# Door-inner.net
KiCad netlist of a schematic drawn in EAGLE
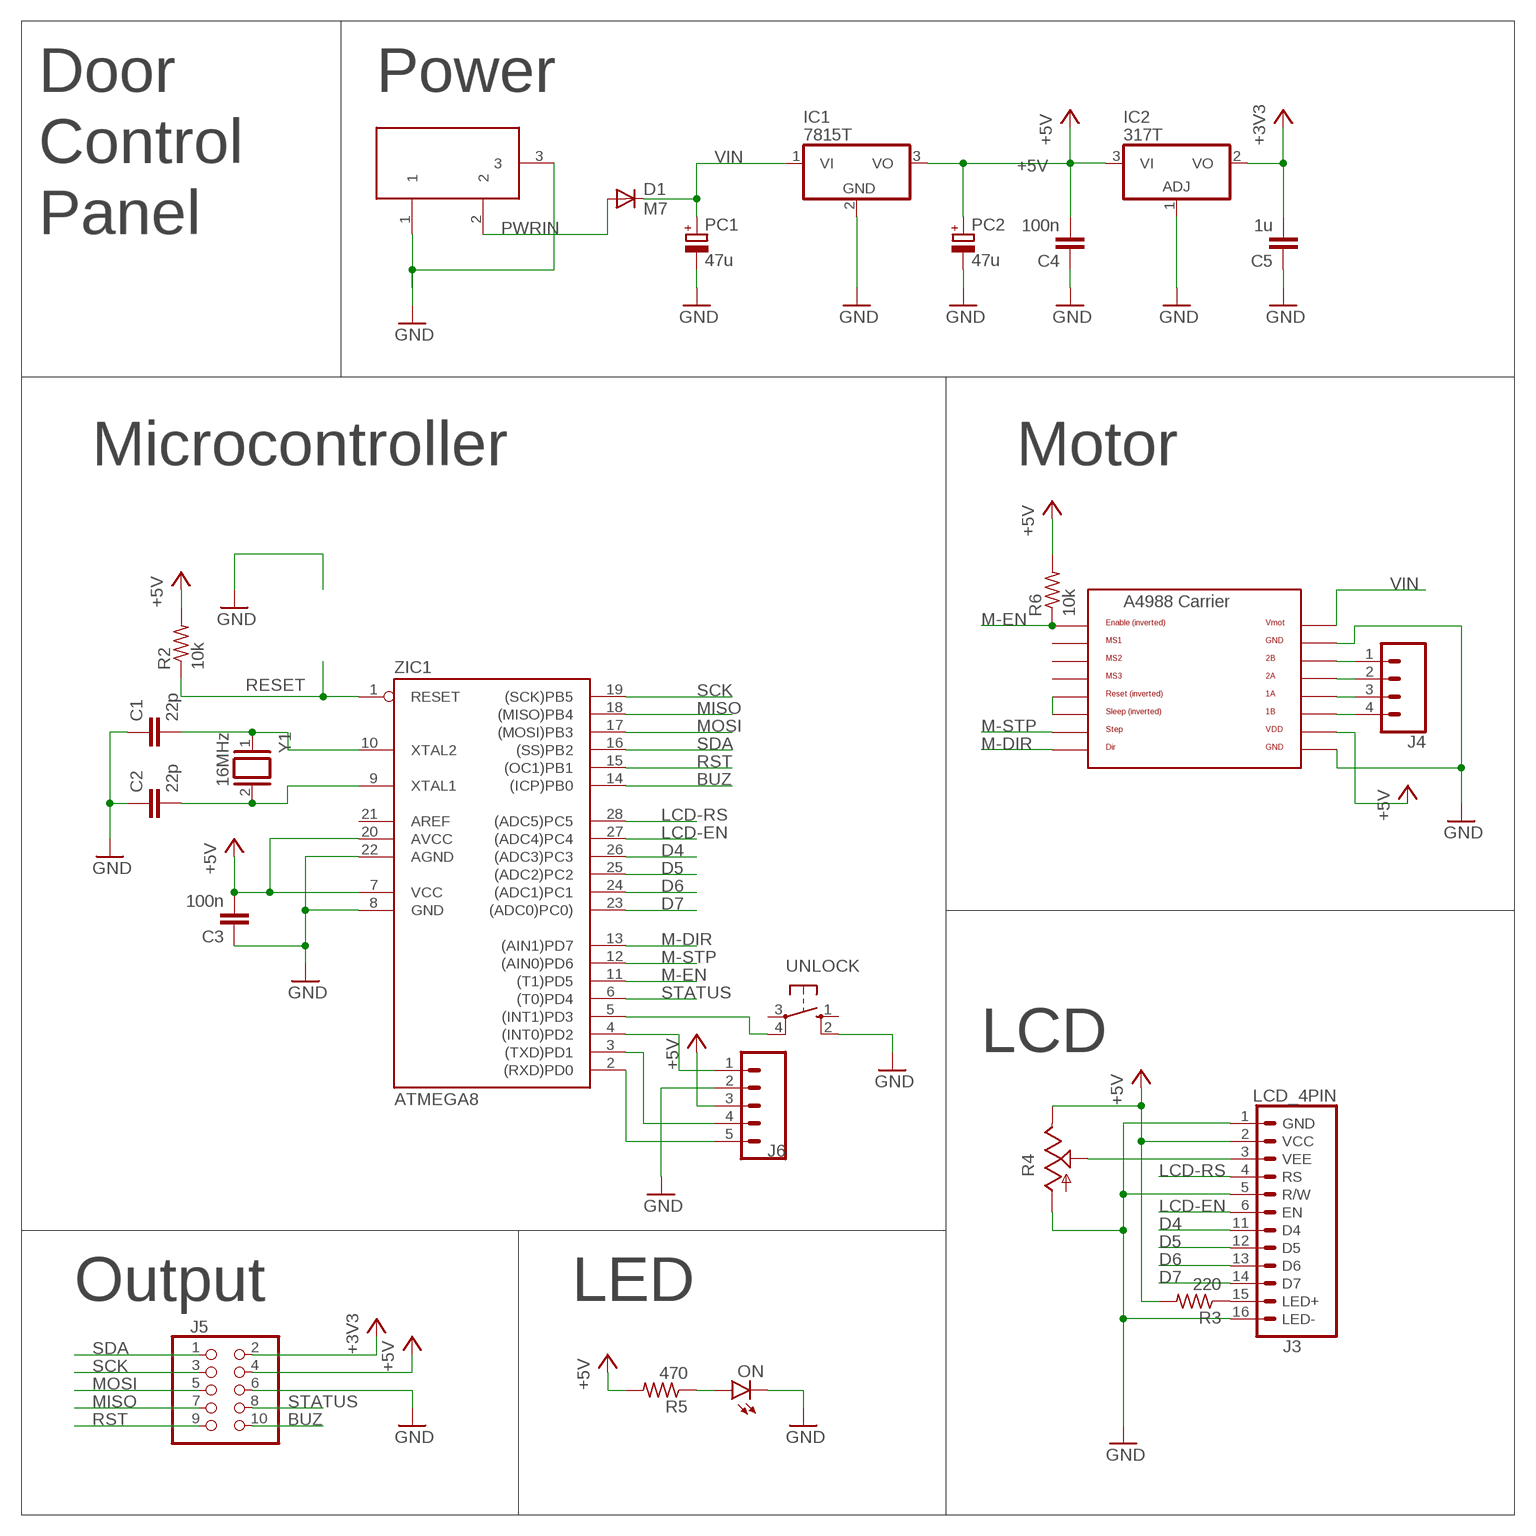
[diagram p0: schematic, sheet 1]

(export (version "E")
  (design (tool "Eeschema 10.0.6"))
  (components
    (comp (ref "C1")
      (value "22p")
      (footprint "eagle-import:C025-030X050")
      (libsource (lib "eagle-import") (part "C-EU025-030X050"))
    )
    (comp (ref "C2")
      (value "22p")
      (footprint "eagle-import:C025-030X050")
      (libsource (lib "eagle-import") (part "C-EU025-030X050"))
    )
    (comp (ref "C3")
      (value "100n")
      (footprint "eagle-import:C050-030X075")
      (libsource (lib "eagle-import") (part "C-EU050-030X075"))
    )
    (comp (ref "C4")
      (value "100n")
      (footprint "eagle-import:C050-030X075")
      (libsource (lib "eagle-import") (part "C-EU050-030X075"))
    )
    (comp (ref "C5")
      (value "1u")
      (footprint "eagle-import:C050-030X075")
      (libsource (lib "eagle-import") (part "C-EU050-030X075"))
    )
    (comp (ref "D1")
      (value "M7")
      (footprint "eagle-import:D-12.5")
      (libsource (lib "eagle-import") (part "DIODE-D-12.5"))
    )
    (comp (ref "IC1")
      (value "7815T")
      (footprint "eagle-import:TO220H")
      (libsource (lib "eagle-import") (part "78T15"))
    )
    (comp (ref "IC2")
      (value "317T")
      (footprint "eagle-import:TO220H")
      (libsource (lib "eagle-import") (part "317T"))
    )
    (comp (ref "J3")
      (value "LCD_4PIN")
      (footprint "eagle-import:LCD-16X2")
      (libsource (lib "eagle-import") (part "LCD_4PIN"))
    )
    (comp (ref "J4")
      (value "CONN_04")
      (footprint "eagle-import:1X04")
      (libsource (lib "eagle-import") (part "CONN_04"))
    )
    (comp (ref "J5")
      (value "PINHD-2X5")
      (footprint "eagle-import:2X05")
      (libsource (lib "eagle-import") (part "PINHD-2X5"))
    )
    (comp (ref "J6")
      (value "CONN_05")
      (footprint "eagle-import:1X05")
      (libsource (lib "eagle-import") (part "CONN_05"))
    )
    (comp (ref "ON")
      (value "LED3MM")
      (footprint "eagle-import:LED3MM")
      (libsource (lib "eagle-import") (part "LED3MM"))
    )
    (comp (ref "PC1")
      (value "47u")
      (footprint "eagle-import:TT2D5")
      (libsource (lib "eagle-import") (part "CPOL-EUTT2D5"))
    )
    (comp (ref "PC2")
      (value "47u")
      (footprint "eagle-import:TT2D5")
      (libsource (lib "eagle-import") (part "CPOL-EUTT2D5"))
    )
    (comp (ref "R2")
      (value "10k")
      (footprint "eagle-import:0207_10")
      (libsource (lib "eagle-import") (part "R-US_0207/10"))
    )
    (comp (ref "R3")
      (value "220")
      (footprint "eagle-import:0207_10")
      (libsource (lib "eagle-import") (part "R-US_0207/10"))
    )
    (comp (ref "R4")
      (value "TRIM_US-S63P")
      (footprint "eagle-import:S63P")
      (libsource (lib "eagle-import") (part "TRIM_US-S63P"))
    )
    (comp (ref "R5")
      (value "470")
      (footprint "eagle-import:0207_10")
      (libsource (lib "eagle-import") (part "R-US_0207/10"))
    )
    (comp (ref "R6")
      (value "10k")
      (footprint "eagle-import:0207_10")
      (libsource (lib "eagle-import") (part "R-US_0207/10"))
    )
    (comp (ref "U$1")
      (value "A4988BREAKOUT")
      (footprint "eagle-import:A4988BREAKOUT")
      (libsource (lib "eagle-import") (part "A4988BREAKOUT"))
    )
    (comp (ref "UNLOCK")
      (value "10-XX")
      (footprint "eagle-import:B3F-10XX")
      (fields (field (name "MPN") "B3F-1000"))
      (libsource (lib "eagle-import") (part "10-XX"))
    )
    (comp (ref "X1")
      (value "POWERSUPPLY_DC21MMX")
      (footprint "eagle-import:POWERSUPPLY_DC-21MM")
      (libsource (lib "eagle-import") (part "POWERSUPPLY_DC21MMX"))
    )
    (comp (ref "Y1")
      (value "16MHz")
      (footprint "eagle-import:QS")
      (libsource (lib "eagle-import") (part "XTAL/S"))
    )
    (comp (ref "ZIC1")
      (value "ATMEGA8")
      (footprint "eagle-import:DIL28-3")
      (libsource (lib "eagle-import") (part "AT90S4433P"))
    )
  )
  (nets
    (net (code "1") (name "+3V3") (class "Default")
      (node (ref "C5") (pin "2") (pinfunction "2_2") (pintype "passive"))
      (node (ref "IC2") (pin "2") (pinfunction "VO_2") (pintype "passive"))
      (node (ref "J5") (pin "2") (pinfunction "2_2") (pintype "passive"))
    )
    (net (code "2") (name "+5V") (class "Default")
      (node (ref "C3") (pin "2") (pinfunction "2_2") (pintype "passive"))
      (node (ref "C4") (pin "2") (pinfunction "2_2") (pintype "passive"))
      (node (ref "IC1") (pin "3") (pinfunction "VO_3") (pintype "passive"))
      (node (ref "IC2") (pin "3") (pinfunction "VI_3") (pintype "input"))
      (node (ref "J3") (pin "2") (pinfunction "VCC_2") (pintype "passive"))
      (node (ref "J5") (pin "4") (pinfunction "4_4") (pintype "passive"))
      (node (ref "J6") (pin "3") (pinfunction "3_3") (pintype "passive"))
      (node (ref "PC2") (pin "+") (pinfunction "+_+") (pintype "passive"))
      (node (ref "R2") (pin "2") (pinfunction "2_2") (pintype "passive"))
      (node (ref "R3") (pin "2") (pinfunction "2_2") (pintype "passive"))
      (node (ref "R4") (pin "E") (pinfunction "E_E") (pintype "passive"))
      (node (ref "R5") (pin "2") (pinfunction "2_2") (pintype "passive"))
      (node (ref "R6") (pin "2") (pinfunction "2_2") (pintype "passive"))
      (node (ref "U$1") (pin "VDD") (pinfunction "VDD_VDD") (pintype "power_in"))
      (node (ref "ZIC1") (pin "20") (pinfunction "AVCC_20") (pintype "power_in"))
      (node (ref "ZIC1") (pin "7") (pinfunction "VCC_7") (pintype "power_in"))
    )
    (net (code "3") (name "/BUZ") (class "Default")
      (node (ref "J5") (pin "10") (pinfunction "10_10") (pintype "passive"))
      (node (ref "ZIC1") (pin "14") (pinfunction "(ICP)PB0_14") (pintype "bidirectional"))
    )
    (net (code "4") (name "/D4") (class "Default")
      (node (ref "J3") (pin "11") (pinfunction "D4_11") (pintype "passive"))
      (node (ref "ZIC1") (pin "26") (pinfunction "(ADC3)PC3_26") (pintype "bidirectional"))
    )
    (net (code "5") (name "/D5") (class "Default")
      (node (ref "J3") (pin "12") (pinfunction "D5_12") (pintype "passive"))
      (node (ref "ZIC1") (pin "25") (pinfunction "(ADC2)PC2_25") (pintype "bidirectional"))
    )
    (net (code "6") (name "/D6") (class "Default")
      (node (ref "J3") (pin "13") (pinfunction "D6_13") (pintype "passive"))
      (node (ref "ZIC1") (pin "24") (pinfunction "(ADC1)PC1_24") (pintype "bidirectional"))
    )
    (net (code "7") (name "/D7") (class "Default")
      (node (ref "J3") (pin "14") (pinfunction "D7_14") (pintype "passive"))
      (node (ref "ZIC1") (pin "23") (pinfunction "(ADC0)PC0)_23") (pintype "bidirectional"))
    )
    (net (code "8") (name "/LCD-EN") (class "Default")
      (node (ref "J3") (pin "6") (pinfunction "EN_6") (pintype "passive"))
      (node (ref "ZIC1") (pin "27") (pinfunction "(ADC4)PC4_27") (pintype "bidirectional"))
    )
    (net (code "9") (name "/LCD-RS") (class "Default")
      (node (ref "J3") (pin "4") (pinfunction "RS_4") (pintype "passive"))
      (node (ref "ZIC1") (pin "28") (pinfunction "(ADC5)PC5_28") (pintype "bidirectional"))
    )
    (net (code "10") (name "/M-DIR") (class "Default")
      (node (ref "U$1") (pin "DIR") (pinfunction "DIR_DIR") (pintype "input"))
      (node (ref "ZIC1") (pin "13") (pinfunction "(AIN1)PD7_13") (pintype "bidirectional"))
    )
    (net (code "11") (name "/M-EN") (class "Default")
      (node (ref "R6") (pin "1") (pinfunction "1_1") (pintype "passive"))
      (node (ref "U$1") (pin "EN") (pinfunction "EN_EN") (pintype "input"))
      (node (ref "ZIC1") (pin "11") (pinfunction "(T1)PD5_11") (pintype "bidirectional"))
    )
    (net (code "12") (name "/M-STP") (class "Default")
      (node (ref "U$1") (pin "STEP") (pinfunction "STEP_STEP") (pintype "input"))
      (node (ref "ZIC1") (pin "12") (pinfunction "(AIN0)PD6_12") (pintype "bidirectional"))
    )
    (net (code "13") (name "/MISO") (class "Default")
      (node (ref "J5") (pin "7") (pinfunction "7_7") (pintype "passive"))
      (node (ref "ZIC1") (pin "18") (pinfunction "(MISO)PB4_18") (pintype "bidirectional"))
    )
    (net (code "14") (name "/MOSI") (class "Default")
      (node (ref "J5") (pin "5") (pinfunction "5_5") (pintype "passive"))
      (node (ref "ZIC1") (pin "17") (pinfunction "(MOSI)PB3_17") (pintype "bidirectional"))
    )
    (net (code "15") (name "/PWRIN") (class "Default")
      (node (ref "D1") (pin "A") (pinfunction "A_A") (pintype "passive"))
      (node (ref "X1") (pin "2") (pinfunction "2_2") (pintype "power_in"))
    )
    (net (code "16") (name "/RESET") (class "Default")
      (node (ref "R2") (pin "1") (pinfunction "1_1") (pintype "passive"))
      (node (ref "ZIC1") (pin "1") (pinfunction "RESET_1") (pintype "input"))
    )
    (net (code "17") (name "/RST") (class "Default")
      (node (ref "J5") (pin "9") (pinfunction "9_9") (pintype "passive"))
      (node (ref "ZIC1") (pin "15") (pinfunction "(OC1)PB1_15") (pintype "bidirectional"))
    )
    (net (code "18") (name "/SCK") (class "Default")
      (node (ref "J5") (pin "3") (pinfunction "3_3") (pintype "passive"))
      (node (ref "ZIC1") (pin "19") (pinfunction "(SCK)PB5_19") (pintype "bidirectional"))
    )
    (net (code "19") (name "/SDA") (class "Default")
      (node (ref "J5") (pin "1") (pinfunction "1_1") (pintype "passive"))
      (node (ref "ZIC1") (pin "16") (pinfunction "(SS)PB2_16") (pintype "bidirectional"))
    )
    (net (code "20") (name "/STATUS") (class "Default")
      (node (ref "J5") (pin "8") (pinfunction "8_8") (pintype "passive"))
      (node (ref "ZIC1") (pin "6") (pinfunction "(T0)PD4_6") (pintype "bidirectional"))
    )
    (net (code "21") (name "/VIN") (class "Default")
      (node (ref "D1") (pin "C") (pinfunction "C_C") (pintype "passive"))
      (node (ref "IC1") (pin "1") (pinfunction "VI_1") (pintype "input"))
      (node (ref "PC1") (pin "+") (pinfunction "+_+") (pintype "passive"))
      (node (ref "U$1") (pin "VMOT") (pinfunction "VMOT_VMOT") (pintype "power_in"))
    )
    (net (code "22") (name "GND") (class "Default")
      (node (ref "C1") (pin "1") (pinfunction "1_1") (pintype "passive"))
      (node (ref "C2") (pin "1") (pinfunction "1_1") (pintype "passive"))
      (node (ref "C3") (pin "1") (pinfunction "1_1") (pintype "passive"))
      (node (ref "C4") (pin "1") (pinfunction "1_1") (pintype "passive"))
      (node (ref "C5") (pin "1") (pinfunction "1_1") (pintype "passive"))
      (node (ref "IC1") (pin "2") (pinfunction "GND_2") (pintype "passive"))
      (node (ref "IC2") (pin "1") (pinfunction "ADJ_1") (pintype "input"))
      (node (ref "J3") (pin "1") (pinfunction "GND_1") (pintype "passive"))
      (node (ref "J3") (pin "16") (pinfunction "LED-_16") (pintype "passive"))
      (node (ref "J3") (pin "5") (pinfunction "R/W_5") (pintype "passive"))
      (node (ref "J5") (pin "6") (pinfunction "6_6") (pintype "passive"))
      (node (ref "J6") (pin "2") (pinfunction "2_2") (pintype "passive"))
      (node (ref "ON") (pin "K") (pinfunction "C_K") (pintype "passive"))
      (node (ref "PC1") (pin "-") (pinfunction "-_-") (pintype "passive"))
      (node (ref "PC2") (pin "-") (pinfunction "-_-") (pintype "passive"))
      (node (ref "R4") (pin "A") (pinfunction "A_A") (pintype "passive"))
      (node (ref "U$1") (pin "GND") (pinfunction "GND_GND") (pintype "power_in"))
      (node (ref "U$1") (pin "GND@0") (pinfunction "GND_GND@0") (pintype "power_in"))
      (node (ref "UNLOCK") (pin "2") (pinfunction "S1_2") (pintype "passive"))
      (node (ref "X1") (pin "1") (pinfunction "1_1") (pintype "power_in"))
      (node (ref "X1") (pin "3") (pinfunction "3_3") (pintype "power_in"))
      (node (ref "ZIC1") (pin "22") (pinfunction "AGND_22") (pintype "power_in"))
      (node (ref "ZIC1") (pin "8") (pinfunction "GND_8") (pintype "power_in"))
    )
    (net (code "23") (name "Net-(J3-LED+)") (class "Default")
      (node (ref "J3") (pin "15") (pinfunction "LED+_15") (pintype "passive"))
      (node (ref "R3") (pin "1") (pinfunction "1_1") (pintype "passive"))
    )
    (net (code "24") (name "Net-(J3-VEE)") (class "Default")
      (node (ref "J3") (pin "3") (pinfunction "VEE_3") (pintype "passive"))
      (node (ref "R4") (pin "S") (pinfunction "S_S") (pintype "passive"))
    )
    (net (code "25") (name "Net-(J4-Pad1)") (class "Default")
      (node (ref "J4") (pin "1") (pinfunction "1_1") (pintype "passive"))
      (node (ref "U$1") (pin "2B") (pinfunction "2B_2B") (pintype "output"))
    )
    (net (code "26") (name "Net-(J4-Pad2)") (class "Default")
      (node (ref "J4") (pin "2") (pinfunction "2_2") (pintype "passive"))
      (node (ref "U$1") (pin "2A") (pinfunction "2A_2A") (pintype "output"))
    )
    (net (code "27") (name "Net-(J4-Pad3)") (class "Default")
      (node (ref "J4") (pin "3") (pinfunction "3_3") (pintype "passive"))
      (node (ref "U$1") (pin "1A") (pinfunction "1A_1A") (pintype "output"))
    )
    (net (code "28") (name "Net-(J4-Pad4)") (class "Default")
      (node (ref "J4") (pin "4") (pinfunction "4_4") (pintype "passive"))
      (node (ref "U$1") (pin "1B") (pinfunction "1B_1B") (pintype "output"))
    )
    (net (code "29") (name "Net-(ON-PadA)") (class "Default")
      (node (ref "ON") (pin "A") (pinfunction "A_A") (pintype "passive"))
      (node (ref "R5") (pin "1") (pinfunction "1_1") (pintype "passive"))
    )
    (net (code "30") (name "Net-(U$1-SLEEP)") (class "Default")
      (node (ref "U$1") (pin "RST") (pinfunction "RST_RST") (pintype "input"))
      (node (ref "U$1") (pin "SLP") (pinfunction "SLEEP_SLP") (pintype "input"))
    )
    (net (code "31") (name "Net-(UNLOCK-P1)") (class "Default")
      (node (ref "UNLOCK") (pin "4") (pinfunction "P1_4") (pintype "passive"))
      (node (ref "ZIC1") (pin "5") (pinfunction "(INT1)PD3_5") (pintype "bidirectional"))
    )
    (net (code "32") (name "Net-(ZIC1-(INT0)PD2)") (class "Default")
      (node (ref "J6") (pin "1") (pinfunction "1_1") (pintype "passive"))
      (node (ref "ZIC1") (pin "4") (pinfunction "(INT0)PD2_4") (pintype "bidirectional"))
    )
    (net (code "33") (name "Net-(ZIC1-(RXD)PD0)") (class "Default")
      (node (ref "J6") (pin "5") (pinfunction "5_5") (pintype "passive"))
      (node (ref "ZIC1") (pin "2") (pinfunction "(RXD)PD0_2") (pintype "bidirectional"))
    )
    (net (code "34") (name "Net-(ZIC1-(TXD)PD1)") (class "Default")
      (node (ref "J6") (pin "4") (pinfunction "4_4") (pintype "passive"))
      (node (ref "ZIC1") (pin "3") (pinfunction "(TXD)PD1_3") (pintype "bidirectional"))
    )
    (net (code "35") (name "Net-(ZIC1-XTAL1)") (class "Default")
      (node (ref "C2") (pin "2") (pinfunction "2_2") (pintype "passive"))
      (node (ref "Y1") (pin "2") (pinfunction "2_2") (pintype "passive"))
      (node (ref "ZIC1") (pin "9") (pinfunction "XTAL1_9") (pintype "bidirectional"))
    )
    (net (code "36") (name "Net-(ZIC1-XTAL2)") (class "Default")
      (node (ref "C1") (pin "2") (pinfunction "2_2") (pintype "passive"))
      (node (ref "Y1") (pin "1") (pinfunction "1_1") (pintype "passive"))
      (node (ref "ZIC1") (pin "10") (pinfunction "XTAL2_10") (pintype "bidirectional"))
    )
    (net (code "37") (name "unconnected-(U$1-PadMS1)") (class "Default")
      (node (ref "U$1") (pin "MS1") (pinfunction "MS1_MS1") (pintype "input"))
    )
    (net (code "38") (name "unconnected-(U$1-PadMS2)") (class "Default")
      (node (ref "U$1") (pin "MS2") (pinfunction "MS2_MS2") (pintype "input"))
    )
    (net (code "39") (name "unconnected-(U$1-PadMS3)") (class "Default")
      (node (ref "U$1") (pin "MS3") (pinfunction "MS3_MS3") (pintype "input"))
    )
    (net (code "40") (name "unconnected-(UNLOCK-P-Pad3)") (class "Default")
      (node (ref "UNLOCK") (pin "3") (pinfunction "P_3") (pintype "passive"))
    )
    (net (code "41") (name "unconnected-(UNLOCK-S-Pad1)") (class "Default")
      (node (ref "UNLOCK") (pin "1") (pinfunction "S_1") (pintype "passive"))
    )
    (net (code "42") (name "unconnected-(ZIC1-AREF-Pad21)") (class "Default")
      (node (ref "ZIC1") (pin "21") (pinfunction "AREF_21") (pintype "passive"))
    )
  )
)
